# speaker.net
KiCad netlist of a schematic drawn in Altium Designer
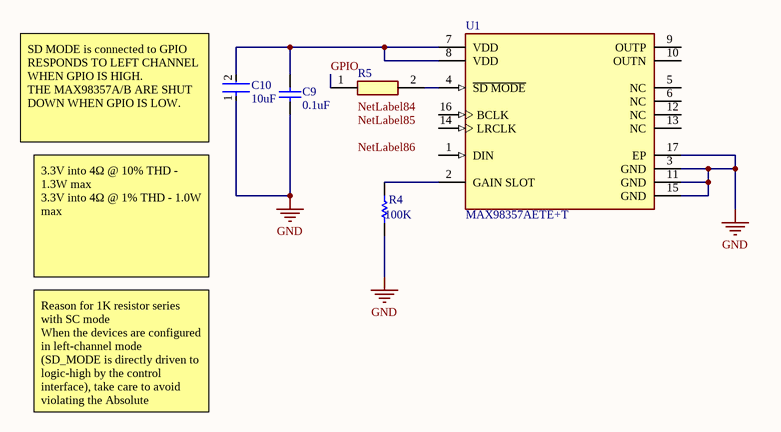
[diagram p0: speaker.SchDoc]

(export (version "E")
  (design (tool "Eeschema 10.0.6"))
  (components
    (comp (ref "C9")
      (value "CL05B104KO5NNNC")
      (footprint "CAPC1050X55X23ML05T13")
      (description "Chip Capacitor, 100 nF, +/- 10%, 16 V, -55 to 125 degC, 0402 (1005 Metric), RoHS, Tape and Reel")
      (fields (field (name "MANUFACTURER") "Samsung Electro-Mechanics") (field (name "CAPACITANCE") "0.1uF"))
      (libsource (lib "Altium Content Vault") (part "CAP-NP-2"))
    )
    (comp (ref "C10")
      (value "CL05A106MP5NUNC")
      (footprint "FP-CL05A106MP5NUNC-MFG")
      (description "CAP CER 10UF 10V X5R 0402")
      (fields
        (field (name "OCTOPART") "https://octopart.com/cl05a106mp5nunc-samsung-22457395")
        (field (name "TOLERANCE") "20%")
        (field (name "CAPACITANCE") "10uF")
      )
      (libsource (lib "Altium Content Vault") (part "b4654b650e69147ec39a6b967a45e02"))
    )
    (comp (ref "R4")
      (value "RC0402FR-07100KL")
      (footprint "RESC1005X40X25NL05T10")
      (fields (field (name "MANUFACTURER") "Yageo / Phycomp") (field (name "RESISTANCE") "100K"))
      (libsource (lib "Altium Content Vault") (part "RES"))
    )
    (comp (ref "R5")
      (value "CR01005-FW-1001GLF")
      (footprint "SamacSys:CR01005FW1001GLF")
      (description "Resistor")
      (fields (field (name "MOUSER PART NUMBER") "576-CR01005-W1001GL"))
      (libsource (lib "*") (part "CR01005-FW-1001GLF"))
    )
    (comp (ref "U1")
      (value "MAX98357AETE+T")
      (footprint "FP-T1633-4-MFG")
      (description "IC AMP CLASS D MONO 3.2W 16TQFN")
      (libsource (lib "Altium Content Vault") (part "902df0143a84dfa2dd990dcc5368a09"))
    )
  )
  (nets
    (net (code "1") (name "/GPIO") (class "Default")
      (node (ref "R5") (pin "1") (pinfunction "1_1") (pintype "passive"))
    )
    (net (code "5") (name "GND") (class "Default")
      (node (ref "C10") (pin "1") (pinfunction "1_1") (pintype "passive"))
      (node (ref "C9") (pin "1") (pinfunction "1_1") (pintype "passive"))
      (node (ref "R4") (pin "1") (pinfunction "1_1") (pintype "passive"))
      (node (ref "U1") (pin "11") (pinfunction "GND_11") (pintype "power_in"))
      (node (ref "U1") (pin "15") (pinfunction "GND_15") (pintype "power_in"))
      (node (ref "U1") (pin "17") (pinfunction "EP_17") (pintype "passive"))
      (node (ref "U1") (pin "3") (pinfunction "GND_3") (pintype "power_in"))
    )
    (net (code "6") (name "Net-(C10-Pad2)") (class "Default")
      (node (ref "C10") (pin "2") (pinfunction "2_2") (pintype "passive"))
      (node (ref "C9") (pin "2") (pinfunction "2_2") (pintype "passive"))
      (node (ref "U1") (pin "7") (pinfunction "VDD_7") (pintype "power_in"))
      (node (ref "U1") (pin "8") (pinfunction "VDD_8") (pintype "power_in"))
    )
    (net (code "7") (name "Net-(U1-GAIN_SLOT)") (class "Default")
      (node (ref "R4") (pin "2") (pinfunction "2_2") (pintype "passive"))
      (node (ref "U1") (pin "2") (pinfunction "GAIN_SLOT_2") (pintype "passive"))
    )
    (net (code "8") (name "Net-(U1-~{SD_MODE})") (class "Default")
      (node (ref "R5") (pin "2") (pinfunction "2_2") (pintype "passive"))
      (node (ref "U1") (pin "4") (pinfunction "~{SD_MODE}_4") (pintype "input"))
    )
    (net (code "9") (name "unconnected-(U1-BCLK-Pad16)") (class "Default")
      (node (ref "U1") (pin "16") (pinfunction "BCLK_16") (pintype "input"))
    )
    (net (code "10") (name "unconnected-(U1-DIN-Pad1)") (class "Default")
      (node (ref "U1") (pin "1") (pinfunction "DIN_1") (pintype "input"))
    )
    (net (code "11") (name "unconnected-(U1-LRCLK-Pad14)") (class "Default")
      (node (ref "U1") (pin "14") (pinfunction "LRCLK_14") (pintype "input"))
    )
    (net (code "12") (name "unconnected-(U1-NC-Pad5)") (class "Default")
      (node (ref "U1") (pin "5") (pinfunction "NC_5") (pintype "passive"))
    )
    (net (code "13") (name "unconnected-(U1-NC-Pad6)") (class "Default")
      (node (ref "U1") (pin "6") (pinfunction "NC_6") (pintype "passive"))
    )
    (net (code "14") (name "unconnected-(U1-NC-Pad12)") (class "Default")
      (node (ref "U1") (pin "12") (pinfunction "NC_12") (pintype "passive"))
    )
    (net (code "15") (name "unconnected-(U1-NC-Pad13)") (class "Default")
      (node (ref "U1") (pin "13") (pinfunction "NC_13") (pintype "passive"))
    )
    (net (code "16") (name "unconnected-(U1-OUTN-Pad10)") (class "Default")
      (node (ref "U1") (pin "10") (pinfunction "OUTN_10") (pintype "passive"))
    )
    (net (code "17") (name "unconnected-(U1-OUTP-Pad9)") (class "Default")
      (node (ref "U1") (pin "9") (pinfunction "OUTP_9") (pintype "passive"))
    )
  )
)
